# Sheet2.net
KiCad netlist of a schematic drawn in Altium Designer
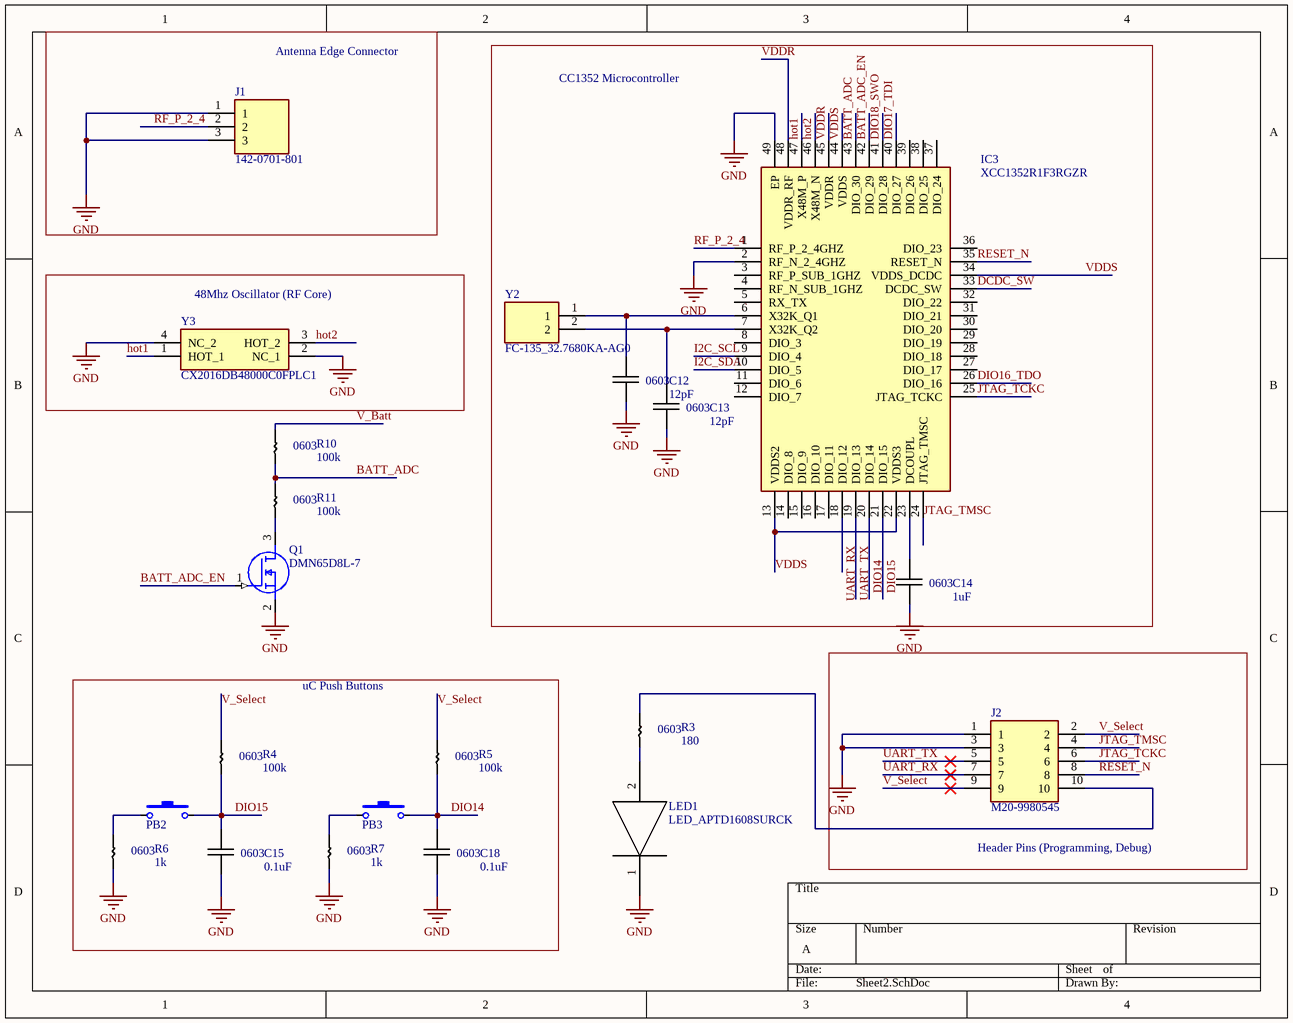
[diagram p0: Sheet2.SchDoc]

(export (version "E")
  (design (tool "Eeschema 10.0.6"))
  (components
    (comp (ref "C12")
      (value "12pF")
      (footprint "0603_SMD")
      (libsource (lib "Enviornmental_Sensor") (part "C_0603"))
    )
    (comp (ref "C13")
      (value "12pF")
      (footprint "0603_SMD")
      (libsource (lib "Enviornmental_Sensor") (part "C_0603"))
    )
    (comp (ref "C14")
      (value "1uF")
      (footprint "0603_SMD")
      (libsource (lib "Enviornmental_Sensor") (part "C_0603"))
    )
    (comp (ref "C15")
      (value "0.1uF")
      (footprint "0603_SMD")
      (libsource (lib "Enviornmental_Sensor") (part "C_0603"))
    )
    (comp (ref "C18")
      (value "0.1uF")
      (footprint "0603_SMD")
      (libsource (lib "Enviornmental_Sensor") (part "C_0603"))
    )
    (comp (ref "IC3")
      (value "XCC1352R1F3RGZR")
      (footprint "SamacSys:QFN50P700X700X100-49N-D")
      (description "Integrated Circuit")
      (libsource (lib "*") (part "XCC1352R1F3RGZR"))
    )
    (comp (ref "J1")
      (value "142-0701-801")
      (footprint "142-0701-851")
      (description "Connector")
      (fields
        (field (name "MOUSER PART NUMBER") "530-142-0701-801")
        (field (name "RS PART NUMBER") "8861070")
      )
      (libsource (lib "Enviornmental_Sensor") (part "142-0701-801"))
    )
    (comp (ref "J2")
      (value "M20-9980545")
      (footprint "SamacSys:HDRV10W80P254_2X5_1270X508X864P")
      (description "Connector")
      (fields
        (field (name "MOUSER PART NUMBER") "855-M20-9980545")
        (field (name "RS PART NUMBER") "6812950P")
      )
      (libsource (lib "*") (part "M20-9980545"))
    )
    (comp (ref "LED1")
      (value "LED_APTD1608SURCK")
      (footprint "LED_APTD1608SURCK")
      (libsource (lib "Enviornmental_Sensor") (part "LED_APTD1608SURCK"))
    )
    (comp (ref "PB2")
      (value "Interface-Push-Button")
      (footprint "INTERFACE-PUSH-BUTTON")
      (description "2.5mm Tall, 2.5N Force, Straight, SMD, Push Button")
      (fields
        (field (name "MANUFACTURER") "C&K Components")
        (field (name "MANUFACTURER PART NUMBER") "PTS820 J25K SMTR LFS")
      )
      (libsource (lib "MasterLib") (part "Interface-Push-Button"))
    )
    (comp (ref "PB3")
      (value "Interface-Push-Button")
      (footprint "INTERFACE-PUSH-BUTTON")
      (description "2.5mm Tall, 2.5N Force, Straight, SMD, Push Button")
      (fields
        (field (name "MANUFACTURER") "C&K Components")
        (field (name "MANUFACTURER PART NUMBER") "PTS820 J25K SMTR LFS")
      )
      (libsource (lib "MasterLib") (part "Interface-Push-Button"))
    )
    (comp (ref "Q1")
      (value "DMN65D8L-7")
      (footprint "SamacSys:SOT96P240X100-3N")
      (description "MOSFET (N-Channel)")
      (fields (field (name "MOUSER PART NUMBER") "621-DMN65D8L-7") (field (name "RS PART NUMBER") "8232952P"))
      (libsource (lib "*") (part "DMN65D8L-7"))
    )
    (comp (ref "R3")
      (value "180")
      (footprint "0603_SMD")
      (libsource (lib "Enviornmental_Sensor") (part "R_0603"))
    )
    (comp (ref "R4")
      (value "100k")
      (footprint "0603_SMD")
      (libsource (lib "Enviornmental_Sensor") (part "R_0603"))
    )
    (comp (ref "R5")
      (value "100k")
      (footprint "0603_SMD")
      (libsource (lib "Enviornmental_Sensor") (part "R_0603"))
    )
    (comp (ref "R6")
      (value "1k")
      (footprint "0603_SMD")
      (libsource (lib "Enviornmental_Sensor") (part "R_0603"))
    )
    (comp (ref "R7")
      (value "1k")
      (footprint "0603_SMD")
      (libsource (lib "Enviornmental_Sensor") (part "R_0603"))
    )
    (comp (ref "R10")
      (value "100k")
      (footprint "0603_SMD")
      (libsource (lib "Enviornmental_Sensor") (part "R_0603"))
    )
    (comp (ref "R11")
      (value "100k")
      (footprint "0603_SMD")
      (libsource (lib "Enviornmental_Sensor") (part "R_0603"))
    )
    (comp (ref "Y2")
      (value "FC-135_32.7680KA-AG0")
      (footprint "SamacSys:FC135327680KAAG0")
      (description "Crystal or Oscillator")
      (fields
        (field (name "MANUFACTURER_PART_NUMBER") "FC-135 32.7680KA-AG0")
        (field (name "MOUSER PART NUMBER") "732-FC135-32.76KAAG0")
      )
      (libsource (lib "*") (part "FC-135_32.7680KA-AG0"))
    )
    (comp (ref "Y3")
      (value "CX2016DB48000C0FPLC1")
      (footprint "SamacSys:CX2016DB48000C0FPLC1")
      (description "Crystal or Oscillator")
      (fields (field (name "MOUSER PART NUMBER") "581-CX2016DB48CFPLC1"))
      (libsource (lib "*") (part "CX2016DB48000C0FPLC1"))
    )
  )
  (nets
    (net (code "1") (name "/BATT_ADC") (class "Default")
      (node (ref "IC3") (pin "43") (pinfunction "DIO_30_43") (pintype "passive"))
      (node (ref "R10") (pin "2") (pinfunction "2_2") (pintype "passive"))
      (node (ref "R11") (pin "1") (pinfunction "1_1") (pintype "passive"))
    )
    (net (code "2") (name "/BATT_ADC_EN") (class "Default")
      (node (ref "IC3") (pin "42") (pinfunction "DIO_29_42") (pintype "passive"))
      (node (ref "Q1") (pin "1") (pinfunction "G_1") (pintype "input"))
    )
    (net (code "3") (name "/DCDC_SW") (class "Default")
      (node (ref "IC3") (pin "33") (pinfunction "DCDC_SW_33") (pintype "passive"))
    )
    (net (code "4") (name "/DIO14") (class "Default")
      (node (ref "C18") (pin "2") (pinfunction "2_2") (pintype "passive"))
      (node (ref "IC3") (pin "20") (pinfunction "DIO_14_20") (pintype "passive"))
      (node (ref "PB3") (pin "2") (pinfunction "2_2") (pintype "passive"))
      (node (ref "R5") (pin "2") (pinfunction "2_2") (pintype "passive"))
    )
    (net (code "5") (name "/DIO15") (class "Default")
      (node (ref "C15") (pin "2") (pinfunction "2_2") (pintype "passive"))
      (node (ref "IC3") (pin "21") (pinfunction "DIO_15_21") (pintype "passive"))
      (node (ref "PB2") (pin "2") (pinfunction "2_2") (pintype "passive"))
      (node (ref "R4") (pin "2") (pinfunction "2_2") (pintype "passive"))
    )
    (net (code "6") (name "/DIO16_TDO") (class "Default")
      (node (ref "IC3") (pin "26") (pinfunction "DIO_16_26") (pintype "passive"))
    )
    (net (code "7") (name "/DIO17_TDI") (class "Default")
      (node (ref "IC3") (pin "40") (pinfunction "DIO_27_40") (pintype "passive"))
    )
    (net (code "8") (name "/DIO18_SWO") (class "Default")
      (node (ref "IC3") (pin "41") (pinfunction "DIO_28_41") (pintype "passive"))
    )
    (net (code "9") (name "/I2C_SCL") (class "Default")
      (node (ref "IC3") (pin "9") (pinfunction "DIO_4_9") (pintype "passive"))
    )
    (net (code "10") (name "/I2C_SDA") (class "Default")
      (node (ref "IC3") (pin "10") (pinfunction "DIO_5_10") (pintype "passive"))
    )
    (net (code "11") (name "/JTAG_TCKC") (class "Default")
      (node (ref "IC3") (pin "25") (pinfunction "JTAG_TCKC_25") (pintype "passive"))
      (node (ref "J2") (pin "6") (pinfunction "6_6") (pintype "passive"))
    )
    (net (code "12") (name "/JTAG_TMSC") (class "Default")
      (node (ref "IC3") (pin "24") (pinfunction "JTAG_TMSC_24") (pintype "passive"))
      (node (ref "J2") (pin "4") (pinfunction "4_4") (pintype "passive"))
    )
    (net (code "13") (name "/RESET_N") (class "Default")
      (node (ref "IC3") (pin "35") (pinfunction "RESET_N_35") (pintype "passive"))
      (node (ref "J2") (pin "8") (pinfunction "8_8") (pintype "passive"))
    )
    (net (code "14") (name "/RF_P_2_4") (class "Default")
      (node (ref "IC3") (pin "1") (pinfunction "RF_P_2_4GHZ_1") (pintype "passive"))
      (node (ref "J1") (pin "2") (pinfunction "2_2") (pintype "passive"))
    )
    (net (code "15") (name "/UART_RX") (class "Default")
      (node (ref "IC3") (pin "18") (pinfunction "DIO_12_18") (pintype "passive"))
      (node (ref "J2") (pin "7") (pinfunction "7_7") (pintype "passive"))
    )
    (net (code "16") (name "/UART_TX") (class "Default")
      (node (ref "IC3") (pin "19") (pinfunction "DIO_13_19") (pintype "passive"))
      (node (ref "J2") (pin "5") (pinfunction "5_5") (pintype "passive"))
    )
    (net (code "17") (name "/VDDR") (class "Default")
      (node (ref "IC3") (pin "45") (pinfunction "VDDR_45") (pintype "passive"))
      (node (ref "IC3") (pin "48") (pinfunction "VDDR_RF_48") (pintype "passive"))
    )
    (net (code "18") (name "/VDDS") (class "Default")
      (node (ref "IC3") (pin "13") (pinfunction "VDDS2_13") (pintype "passive"))
      (node (ref "IC3") (pin "22") (pinfunction "VDDS3_22") (pintype "passive"))
      (node (ref "IC3") (pin "34") (pinfunction "VDDS_DCDC_34") (pintype "passive"))
      (node (ref "IC3") (pin "44") (pinfunction "VDDS_44") (pintype "passive"))
    )
    (net (code "19") (name "/V_Batt") (class "Default")
      (node (ref "R10") (pin "1") (pinfunction "1_1") (pintype "passive"))
    )
    (net (code "20") (name "/V_Select") (class "Default")
      (node (ref "J2") (pin "2") (pinfunction "2_2") (pintype "passive"))
      (node (ref "J2") (pin "9") (pinfunction "9_9") (pintype "passive"))
      (node (ref "R4") (pin "1") (pinfunction "1_1") (pintype "passive"))
      (node (ref "R5") (pin "1") (pinfunction "1_1") (pintype "passive"))
    )
    (net (code "21") (name "/hot1") (class "Default")
      (node (ref "IC3") (pin "47") (pinfunction "X48M_P_47") (pintype "passive"))
      (node (ref "Y3") (pin "1") (pinfunction "HOT_1_1") (pintype "passive"))
    )
    (net (code "22") (name "/hot2") (class "Default")
      (node (ref "IC3") (pin "46") (pinfunction "X48M_N_46") (pintype "passive"))
      (node (ref "Y3") (pin "3") (pinfunction "HOT_2_3") (pintype "passive"))
    )
    (net (code "23") (name "GND") (class "Default")
      (node (ref "C12") (pin "1") (pinfunction "1_1") (pintype "passive"))
      (node (ref "C13") (pin "1") (pinfunction "1_1") (pintype "passive"))
      (node (ref "C14") (pin "1") (pinfunction "1_1") (pintype "passive"))
      (node (ref "C15") (pin "1") (pinfunction "1_1") (pintype "passive"))
      (node (ref "C18") (pin "1") (pinfunction "1_1") (pintype "passive"))
      (node (ref "IC3") (pin "2") (pinfunction "RF_N_2_4GHZ_2") (pintype "passive"))
      (node (ref "IC3") (pin "49") (pinfunction "EP_49") (pintype "passive"))
      (node (ref "J1") (pin "1") (pinfunction "1_1") (pintype "passive"))
      (node (ref "J1") (pin "3") (pinfunction "3_3") (pintype "passive"))
      (node (ref "J2") (pin "1") (pinfunction "1_1") (pintype "passive"))
      (node (ref "J2") (pin "3") (pinfunction "3_3") (pintype "passive"))
      (node (ref "LED1") (pin "1") (pinfunction "1_1") (pintype "passive"))
      (node (ref "Q1") (pin "2") (pinfunction "S_2") (pintype "passive"))
      (node (ref "R6") (pin "2") (pinfunction "2_2") (pintype "passive"))
      (node (ref "R7") (pin "2") (pinfunction "2_2") (pintype "passive"))
      (node (ref "Y3") (pin "2") (pinfunction "NC_1_2") (pintype "passive"))
      (node (ref "Y3") (pin "4") (pinfunction "NC_2_4") (pintype "passive"))
    )
    (net (code "24") (name "Net-(IC3-DCOUPL)") (class "Default")
      (node (ref "C14") (pin "2") (pinfunction "2_2") (pintype "passive"))
      (node (ref "IC3") (pin "23") (pinfunction "DCOUPL_23") (pintype "passive"))
    )
    (net (code "25") (name "Net-(IC3-X32K_Q1)") (class "Default")
      (node (ref "C12") (pin "2") (pinfunction "2_2") (pintype "passive"))
      (node (ref "IC3") (pin "6") (pinfunction "X32K_Q1_6") (pintype "passive"))
      (node (ref "Y2") (pin "1") (pinfunction "1_1") (pintype "passive"))
    )
    (net (code "26") (name "Net-(IC3-X32K_Q2)") (class "Default")
      (node (ref "C13") (pin "2") (pinfunction "2_2") (pintype "passive"))
      (node (ref "IC3") (pin "7") (pinfunction "X32K_Q2_7") (pintype "passive"))
      (node (ref "Y2") (pin "2") (pinfunction "2_2") (pintype "passive"))
    )
    (net (code "27") (name "Net-(J2-Pad10)") (class "Default")
      (node (ref "J2") (pin "10") (pinfunction "10_10") (pintype "passive"))
      (node (ref "R3") (pin "1") (pinfunction "1_1") (pintype "passive"))
    )
    (net (code "28") (name "Net-(LED1-Pad2)") (class "Default")
      (node (ref "LED1") (pin "2") (pinfunction "2_2") (pintype "passive"))
      (node (ref "R3") (pin "2") (pinfunction "2_2") (pintype "passive"))
    )
    (net (code "29") (name "Net-(PB2-Pad1)") (class "Default")
      (node (ref "PB2") (pin "1") (pinfunction "1_1") (pintype "passive"))
      (node (ref "R6") (pin "1") (pinfunction "1_1") (pintype "passive"))
    )
    (net (code "30") (name "Net-(PB3-Pad1)") (class "Default")
      (node (ref "PB3") (pin "1") (pinfunction "1_1") (pintype "passive"))
      (node (ref "R7") (pin "1") (pinfunction "1_1") (pintype "passive"))
    )
    (net (code "31") (name "Net-(Q1-D)") (class "Default")
      (node (ref "Q1") (pin "3") (pinfunction "D_3") (pintype "passive"))
      (node (ref "R11") (pin "2") (pinfunction "2_2") (pintype "passive"))
    )
    (net (code "32") (name "unconnected-(IC3-DIO_3-Pad8)") (class "Default")
      (node (ref "IC3") (pin "8") (pinfunction "DIO_3_8") (pintype "passive"))
    )
    (net (code "33") (name "unconnected-(IC3-DIO_6-Pad11)") (class "Default")
      (node (ref "IC3") (pin "11") (pinfunction "DIO_6_11") (pintype "passive"))
    )
    (net (code "34") (name "unconnected-(IC3-DIO_7-Pad12)") (class "Default")
      (node (ref "IC3") (pin "12") (pinfunction "DIO_7_12") (pintype "passive"))
    )
    (net (code "35") (name "unconnected-(IC3-DIO_8-Pad14)") (class "Default")
      (node (ref "IC3") (pin "14") (pinfunction "DIO_8_14") (pintype "passive"))
    )
    (net (code "36") (name "unconnected-(IC3-DIO_9-Pad15)") (class "Default")
      (node (ref "IC3") (pin "15") (pinfunction "DIO_9_15") (pintype "passive"))
    )
    (net (code "37") (name "unconnected-(IC3-DIO_10-Pad16)") (class "Default")
      (node (ref "IC3") (pin "16") (pinfunction "DIO_10_16") (pintype "passive"))
    )
    (net (code "38") (name "unconnected-(IC3-DIO_11-Pad17)") (class "Default")
      (node (ref "IC3") (pin "17") (pinfunction "DIO_11_17") (pintype "passive"))
    )
    (net (code "39") (name "unconnected-(IC3-DIO_17-Pad27)") (class "Default")
      (node (ref "IC3") (pin "27") (pinfunction "DIO_17_27") (pintype "passive"))
    )
    (net (code "40") (name "unconnected-(IC3-DIO_18-Pad28)") (class "Default")
      (node (ref "IC3") (pin "28") (pinfunction "DIO_18_28") (pintype "passive"))
    )
    (net (code "41") (name "unconnected-(IC3-DIO_19-Pad29)") (class "Default")
      (node (ref "IC3") (pin "29") (pinfunction "DIO_19_29") (pintype "passive"))
    )
    (net (code "42") (name "unconnected-(IC3-DIO_20-Pad30)") (class "Default")
      (node (ref "IC3") (pin "30") (pinfunction "DIO_20_30") (pintype "passive"))
    )
    (net (code "43") (name "unconnected-(IC3-DIO_21-Pad31)") (class "Default")
      (node (ref "IC3") (pin "31") (pinfunction "DIO_21_31") (pintype "passive"))
    )
    (net (code "44") (name "unconnected-(IC3-DIO_22-Pad32)") (class "Default")
      (node (ref "IC3") (pin "32") (pinfunction "DIO_22_32") (pintype "passive"))
    )
    (net (code "45") (name "unconnected-(IC3-DIO_23-Pad36)") (class "Default")
      (node (ref "IC3") (pin "36") (pinfunction "DIO_23_36") (pintype "passive"))
    )
    (net (code "46") (name "unconnected-(IC3-DIO_24-Pad37)") (class "Default")
      (node (ref "IC3") (pin "37") (pinfunction "DIO_24_37") (pintype "passive"))
    )
    (net (code "47") (name "unconnected-(IC3-DIO_25-Pad38)") (class "Default")
      (node (ref "IC3") (pin "38") (pinfunction "DIO_25_38") (pintype "passive"))
    )
    (net (code "48") (name "unconnected-(IC3-DIO_26-Pad39)") (class "Default")
      (node (ref "IC3") (pin "39") (pinfunction "DIO_26_39") (pintype "passive"))
    )
    (net (code "49") (name "unconnected-(IC3-RF_N_SUB_1GHZ-Pad4)") (class "Default")
      (node (ref "IC3") (pin "4") (pinfunction "RF_N_SUB_1GHZ_4") (pintype "passive"))
    )
    (net (code "50") (name "unconnected-(IC3-RF_P_SUB_1GHZ-Pad3)") (class "Default")
      (node (ref "IC3") (pin "3") (pinfunction "RF_P_SUB_1GHZ_3") (pintype "passive"))
    )
    (net (code "51") (name "unconnected-(IC3-RX_TX-Pad5)") (class "Default")
      (node (ref "IC3") (pin "5") (pinfunction "RX_TX_5") (pintype "passive"))
    )
  )
)
